# danger_danger_psu-mk-5.net
KiCad netlist of a schematic drawn in EAGLE
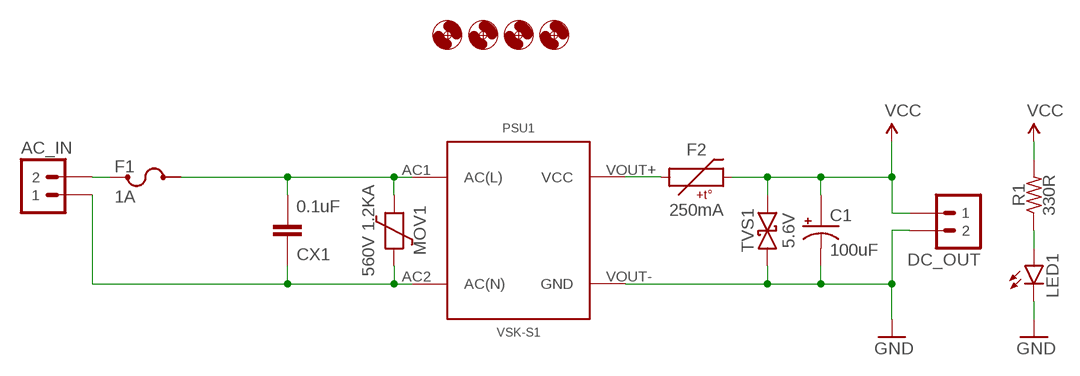
[diagram p0: schematic, sheet 1]

(export (version "E")
  (design (tool "Eeschema 10.0.6"))
  (components
    (comp (ref "AC_IN")
      (value "M023.5MM")
      (footprint "eagle-import:SCREWTERMINAL-3.5MM-2")
      (libsource (lib "eagle-import") (part "M023.5MM"))
    )
    (comp (ref "C1")
      (value "100uF")
      (footprint "eagle-import:E2,5-6")
      (libsource (lib "eagle-import") (part "CAPACITOR-POLARIZEDE2.5-6"))
    )
    (comp (ref "CX1")
      (value "0.1uF")
      (footprint "eagle-import:XC10B6")
      (libsource (lib "eagle-import") (part "CXXC10B6"))
    )
    (comp (ref "DC_OUT")
      (value "M02JST-PTH-VERT")
      (footprint "eagle-import:JST-2-PH-VERT-PTH")
      (libsource (lib "eagle-import") (part "M02JST-PTH-VERT"))
    )
    (comp (ref "F1")
      (value "1A")
      (footprint "eagle-import:KEYSTONE-MINI-AUTO-FUSE-HOLDER")
      (libsource (lib "eagle-import") (part "FUSEMINI-AUTO"))
    )
    (comp (ref "F2")
      (value "250mA")
      (footprint "eagle-import:PTC-PTH-5.08MM")
      (libsource (lib "eagle-import") (part "PTCPTH-5.08MM"))
    )
    (comp (ref "H1")
      (value "HOLE#2")
      (footprint "eagle-import:HOLE-#2")
      (libsource (lib "eagle-import") (part "HOLE#2"))
    )
    (comp (ref "H2")
      (value "HOLE#2")
      (footprint "eagle-import:HOLE-#2")
      (libsource (lib "eagle-import") (part "HOLE#2"))
    )
    (comp (ref "H3")
      (value "HOLE#2")
      (footprint "eagle-import:HOLE-#2")
      (libsource (lib "eagle-import") (part "HOLE#2"))
    )
    (comp (ref "H4")
      (value "HOLE#2")
      (footprint "eagle-import:HOLE-#2")
      (libsource (lib "eagle-import") (part "HOLE#2"))
    )
    (comp (ref "LED1")
      (value "LED3MM")
      (footprint "eagle-import:LED3MM")
      (libsource (lib "eagle-import") (part "LED3MM"))
    )
    (comp (ref "MOV1")
      (value "560V 1.2KA")
      (footprint "eagle-import:VAR-5.08MM-PTH")
      (libsource (lib "eagle-import") (part "VARISITORVAR-5.08MM-PTH"))
    )
    (comp (ref "PSU1")
      (value "VSK-S1")
      (footprint "eagle-import:VSK-S1")
      (libsource (lib "eagle-import") (part "VSK-S1"))
    )
    (comp (ref "R1")
      (value "330R")
      (footprint "eagle-import:RESISTOR-AXIAL-PTH-5.08MM")
      (libsource (lib "eagle-import") (part "RESISTORPTH-AXIAL-5.08MM"))
    )
    (comp (ref "TVS1")
      (value "5.6V")
      (footprint "eagle-import:DO-41-TVS-BI-10.16MM")
      (libsource (lib "eagle-import") (part "TVSDO-41-10.16MM"))
    )
  )
  (nets
    (net (code "1") (name "GND") (class "Default")
      (node (ref "C1") (pin "-") (pinfunction "-_-") (pintype "passive"))
      (node (ref "DC_OUT") (pin "2") (pinfunction "2_2") (pintype "passive"))
      (node (ref "LED1") (pin "K") (pinfunction "C_K") (pintype "passive"))
      (node (ref "PSU1") (pin "VOUT-") (pinfunction "GND_VOUT-") (pintype "bidirectional"))
      (node (ref "TVS1") (pin "P$2") (pinfunction "2_P$2") (pintype "passive"))
    )
    (net (code "2") (name "Net-(AC_IN-Pad2)") (class "Default")
      (node (ref "AC_IN") (pin "2") (pinfunction "2_2") (pintype "passive"))
      (node (ref "F1") (pin "P1@1") (pinfunction "1_P1@1") (pintype "passive"))
      (node (ref "F1") (pin "P1@2") (pinfunction "1_P1@2") (pintype "passive"))
    )
    (net (code "3") (name "Net-(F2-1)") (class "Default")
      (node (ref "F2") (pin "P$1") (pinfunction "1_P$1") (pintype "passive"))
      (node (ref "PSU1") (pin "VOUT+") (pinfunction "VCC_VOUT+") (pintype "bidirectional"))
    )
    (net (code "4") (name "Net-(MOV1-P$1)") (class "Default")
      (node (ref "CX1") (pin "2") (pinfunction "2_2") (pintype "passive"))
      (node (ref "F1") (pin "P2@1") (pinfunction "2_P2@1") (pintype "passive"))
      (node (ref "F1") (pin "P2@2") (pinfunction "2_P2@2") (pintype "passive"))
      (node (ref "MOV1") (pin "1") (pinfunction "P$1_1") (pintype "passive"))
      (node (ref "PSU1") (pin "AC1") (pinfunction "AC(L)_AC1") (pintype "bidirectional"))
    )
    (net (code "5") (name "Net-(MOV1-P$2)") (class "Default")
      (node (ref "AC_IN") (pin "1") (pinfunction "1_1") (pintype "passive"))
      (node (ref "CX1") (pin "1") (pinfunction "1_1") (pintype "passive"))
      (node (ref "MOV1") (pin "2") (pinfunction "P$2_2") (pintype "passive"))
      (node (ref "PSU1") (pin "AC2") (pinfunction "AC(N)_AC2") (pintype "bidirectional"))
    )
    (net (code "6") (name "Net-(R1-1)") (class "Default")
      (node (ref "LED1") (pin "A") (pinfunction "A_A") (pintype "passive"))
      (node (ref "R1") (pin "P$1") (pinfunction "1_P$1") (pintype "passive"))
    )
    (net (code "7") (name "VCC") (class "Default")
      (node (ref "C1") (pin "+") (pinfunction "+_+") (pintype "passive"))
      (node (ref "DC_OUT") (pin "1") (pinfunction "1_1") (pintype "passive"))
      (node (ref "F2") (pin "P$2") (pinfunction "2_P$2") (pintype "passive"))
      (node (ref "R1") (pin "P$2") (pinfunction "2_P$2") (pintype "passive"))
      (node (ref "TVS1") (pin "P$1") (pinfunction "1_P$1") (pintype "passive"))
    )
  )
)
